# Project_FALLOUT_HK_PAD.net
KiCad netlist of a schematic drawn in EasyEDA Pro
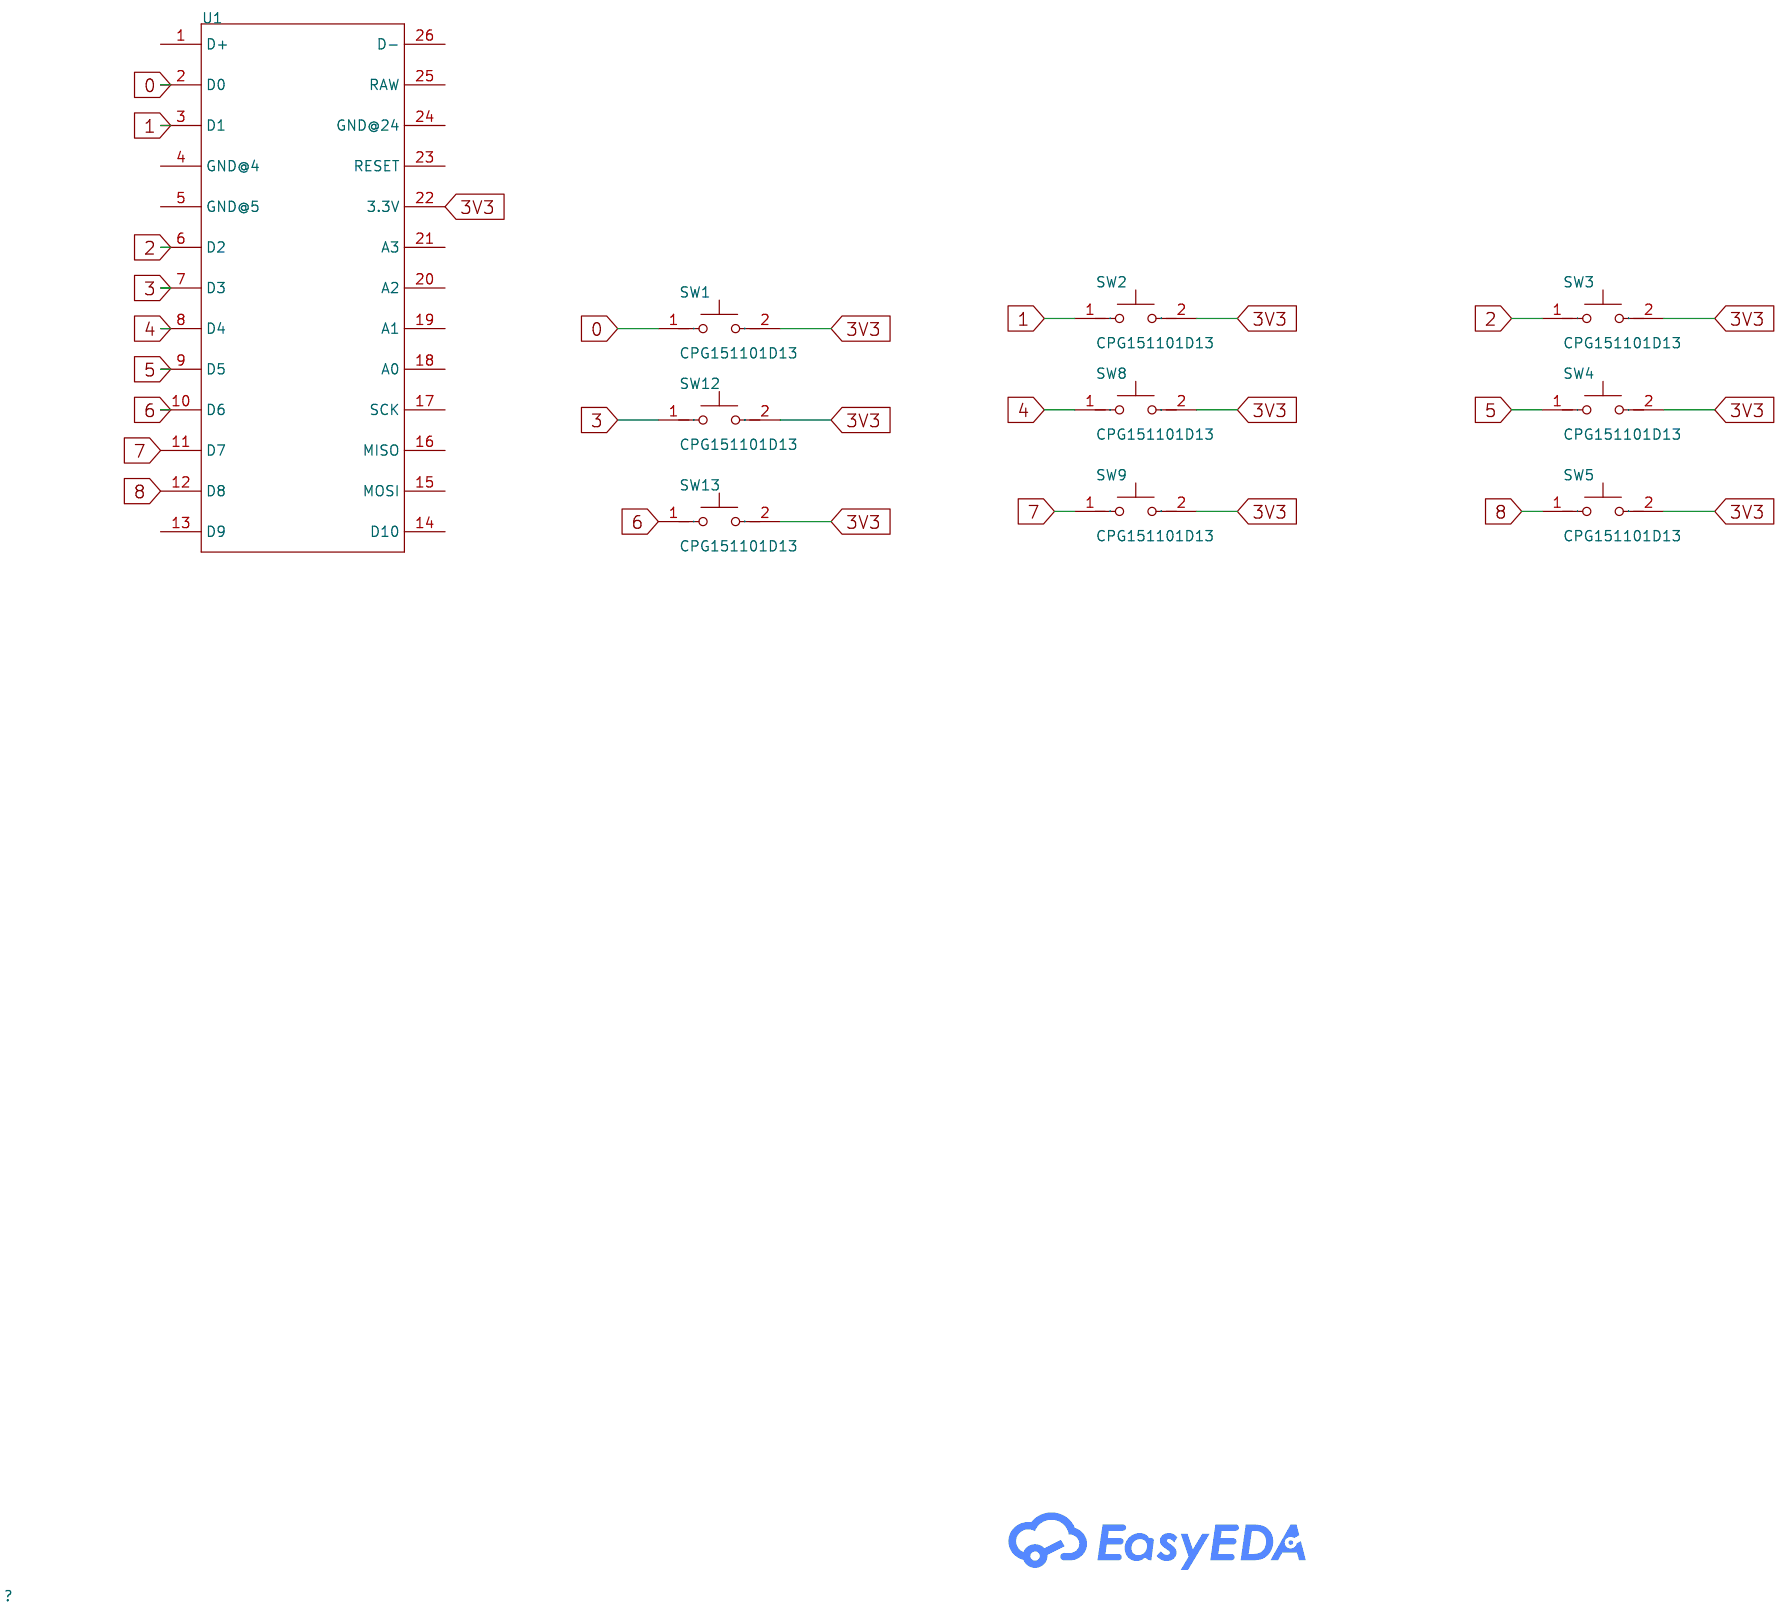
[diagram p0: schematic sheet]

(export (version "E")
  (design (tool "Eeschema 10.0.6"))
  (components
    (comp (ref "SW1")
      (value "CPG151101D13")
      (footprint "easyedapro:KEY-TH_CPG1511F01S0X")
      (fields (field (name "Manufacturer") "HanElectricity(瀚源)"))
      (libsource (lib "easyedapro") (part "CPG1511F01S03"))
    )
    (comp (ref "SW2")
      (value "CPG151101D13")
      (footprint "easyedapro:KEY-TH_CPG1511F01S0X")
      (fields (field (name "Manufacturer") "HanElectricity(瀚源)"))
      (libsource (lib "easyedapro") (part "CPG1511F01S03"))
    )
    (comp (ref "SW3")
      (value "CPG151101D13")
      (footprint "easyedapro:KEY-TH_CPG1511F01S0X")
      (fields (field (name "Manufacturer") "HanElectricity(瀚源)"))
      (libsource (lib "easyedapro") (part "CPG1511F01S03"))
    )
    (comp (ref "SW4")
      (value "CPG151101D13")
      (footprint "easyedapro:KEY-TH_CPG1511F01S0X")
      (fields (field (name "Manufacturer") "HanElectricity(瀚源)"))
      (libsource (lib "easyedapro") (part "CPG1511F01S03"))
    )
    (comp (ref "SW5")
      (value "CPG151101D13")
      (footprint "easyedapro:KEY-TH_CPG1511F01S0X")
      (fields (field (name "Manufacturer") "HanElectricity(瀚源)"))
      (libsource (lib "easyedapro") (part "CPG1511F01S03"))
    )
    (comp (ref "SW8")
      (value "CPG151101D13")
      (footprint "easyedapro:KEY-TH_CPG1511F01S0X")
      (fields (field (name "Manufacturer") "HanElectricity(瀚源)"))
      (libsource (lib "easyedapro") (part "CPG1511F01S03"))
    )
    (comp (ref "SW9")
      (value "CPG151101D13")
      (footprint "easyedapro:KEY-TH_CPG1511F01S0X")
      (fields (field (name "Manufacturer") "HanElectricity(瀚源)"))
      (libsource (lib "easyedapro") (part "CPG1511F01S03"))
    )
    (comp (ref "SW12")
      (value "CPG151101D13")
      (footprint "easyedapro:KEY-TH_CPG1511F01S0X")
      (fields (field (name "Manufacturer") "HanElectricity(瀚源)"))
      (libsource (lib "easyedapro") (part "CPG1511F01S03"))
    )
    (comp (ref "SW13")
      (value "CPG151101D13")
      (footprint "easyedapro:KEY-TH_CPG1511F01S0X")
      (fields (field (name "Manufacturer") "HanElectricity(瀚源)"))
      (libsource (lib "easyedapro") (part "CPG1511F01S03"))
    )
    (comp (ref "U1") (value "~") (libsource (lib "easyedapro") (part "KB2040")))
  )
  (nets
    (net (code "1") (name "0") (class "Default")
      (node (ref "SW1") (pin "1") (pinfunction "1_1") (pintype "unspecified"))
      (node (ref "U1") (pin "2") (pinfunction "D0_2") (pintype "bidirectional"))
    )
    (net (code "2") (name "1") (class "Default")
      (node (ref "SW2") (pin "1") (pinfunction "1_1") (pintype "unspecified"))
      (node (ref "U1") (pin "3") (pinfunction "D1_3") (pintype "bidirectional"))
    )
    (net (code "3") (name "2") (class "Default")
      (node (ref "SW3") (pin "1") (pinfunction "1_1") (pintype "unspecified"))
      (node (ref "U1") (pin "6") (pinfunction "D2_6") (pintype "bidirectional"))
    )
    (net (code "4") (name "3") (class "Default")
      (node (ref "SW12") (pin "1") (pinfunction "1_1") (pintype "unspecified"))
      (node (ref "U1") (pin "7") (pinfunction "D3_7") (pintype "bidirectional"))
    )
    (net (code "5") (name "3V3") (class "Default")
      (node (ref "SW1") (pin "2") (pinfunction "2_2") (pintype "unspecified"))
      (node (ref "SW12") (pin "2") (pinfunction "2_2") (pintype "unspecified"))
      (node (ref "SW13") (pin "2") (pinfunction "2_2") (pintype "unspecified"))
      (node (ref "SW2") (pin "2") (pinfunction "2_2") (pintype "unspecified"))
      (node (ref "SW3") (pin "2") (pinfunction "2_2") (pintype "unspecified"))
      (node (ref "SW4") (pin "2") (pinfunction "2_2") (pintype "unspecified"))
      (node (ref "SW5") (pin "2") (pinfunction "2_2") (pintype "unspecified"))
      (node (ref "SW8") (pin "2") (pinfunction "2_2") (pintype "unspecified"))
      (node (ref "SW9") (pin "2") (pinfunction "2_2") (pintype "unspecified"))
      (node (ref "U1") (pin "22") (pinfunction "3.3V_22") (pintype "bidirectional"))
    )
    (net (code "6") (name "4") (class "Default")
      (node (ref "SW8") (pin "1") (pinfunction "1_1") (pintype "unspecified"))
      (node (ref "U1") (pin "8") (pinfunction "D4_8") (pintype "bidirectional"))
    )
    (net (code "7") (name "5") (class "Default")
      (node (ref "SW4") (pin "1") (pinfunction "1_1") (pintype "unspecified"))
      (node (ref "U1") (pin "9") (pinfunction "D5_9") (pintype "bidirectional"))
    )
    (net (code "8") (name "6") (class "Default")
      (node (ref "SW13") (pin "1") (pinfunction "1_1") (pintype "unspecified"))
      (node (ref "U1") (pin "10") (pinfunction "D6_10") (pintype "bidirectional"))
    )
    (net (code "9") (name "7") (class "Default")
      (node (ref "SW9") (pin "1") (pinfunction "1_1") (pintype "unspecified"))
      (node (ref "U1") (pin "11") (pinfunction "D7_11") (pintype "bidirectional"))
    )
    (net (code "10") (name "8") (class "Default")
      (node (ref "SW5") (pin "1") (pinfunction "1_1") (pintype "unspecified"))
      (node (ref "U1") (pin "12") (pinfunction "D8_12") (pintype "bidirectional"))
    )
    (net (code "11") (name "unconnected-(U1-A0-Pad18)") (class "Default")
      (node (ref "U1") (pin "18") (pinfunction "A0_18") (pintype "bidirectional"))
    )
    (net (code "12") (name "unconnected-(U1-A1-Pad19)") (class "Default")
      (node (ref "U1") (pin "19") (pinfunction "A1_19") (pintype "bidirectional"))
    )
    (net (code "13") (name "unconnected-(U1-A2-Pad20)") (class "Default")
      (node (ref "U1") (pin "20") (pinfunction "A2_20") (pintype "bidirectional"))
    )
    (net (code "14") (name "unconnected-(U1-A3-Pad21)") (class "Default")
      (node (ref "U1") (pin "21") (pinfunction "A3_21") (pintype "bidirectional"))
    )
    (net (code "15") (name "unconnected-(U1-D+-Pad1)") (class "Default")
      (node (ref "U1") (pin "1") (pinfunction "D+_1") (pintype "bidirectional"))
    )
    (net (code "16") (name "unconnected-(U1-D--Pad26)") (class "Default")
      (node (ref "U1") (pin "26") (pinfunction "D-_26") (pintype "bidirectional"))
    )
    (net (code "17") (name "unconnected-(U1-D9-Pad13)") (class "Default")
      (node (ref "U1") (pin "13") (pinfunction "D9_13") (pintype "bidirectional"))
    )
    (net (code "18") (name "unconnected-(U1-D10-Pad14)") (class "Default")
      (node (ref "U1") (pin "14") (pinfunction "D10_14") (pintype "bidirectional"))
    )
    (net (code "19") (name "unconnected-(U1-GND@4-Pad4)") (class "Default")
      (node (ref "U1") (pin "4") (pinfunction "GND@4_4") (pintype "bidirectional"))
    )
    (net (code "20") (name "unconnected-(U1-GND@5-Pad5)") (class "Default")
      (node (ref "U1") (pin "5") (pinfunction "GND@5_5") (pintype "bidirectional"))
    )
    (net (code "21") (name "unconnected-(U1-GND@24-Pad24)") (class "Default")
      (node (ref "U1") (pin "24") (pinfunction "GND@24_24") (pintype "bidirectional"))
    )
    (net (code "22") (name "unconnected-(U1-MISO-Pad16)") (class "Default")
      (node (ref "U1") (pin "16") (pinfunction "MISO_16") (pintype "bidirectional"))
    )
    (net (code "23") (name "unconnected-(U1-MOSI-Pad15)") (class "Default")
      (node (ref "U1") (pin "15") (pinfunction "MOSI_15") (pintype "bidirectional"))
    )
    (net (code "24") (name "unconnected-(U1-RAW-Pad25)") (class "Default")
      (node (ref "U1") (pin "25") (pinfunction "RAW_25") (pintype "bidirectional"))
    )
    (net (code "25") (name "unconnected-(U1-RESET-Pad23)") (class "Default")
      (node (ref "U1") (pin "23") (pinfunction "RESET_23") (pintype "bidirectional"))
    )
    (net (code "26") (name "unconnected-(U1-SCK-Pad17)") (class "Default")
      (node (ref "U1") (pin "17") (pinfunction "SCK_17") (pintype "bidirectional"))
    )
  )
)
